# current-sensor.net
KiCad netlist of a schematic drawn in EAGLE
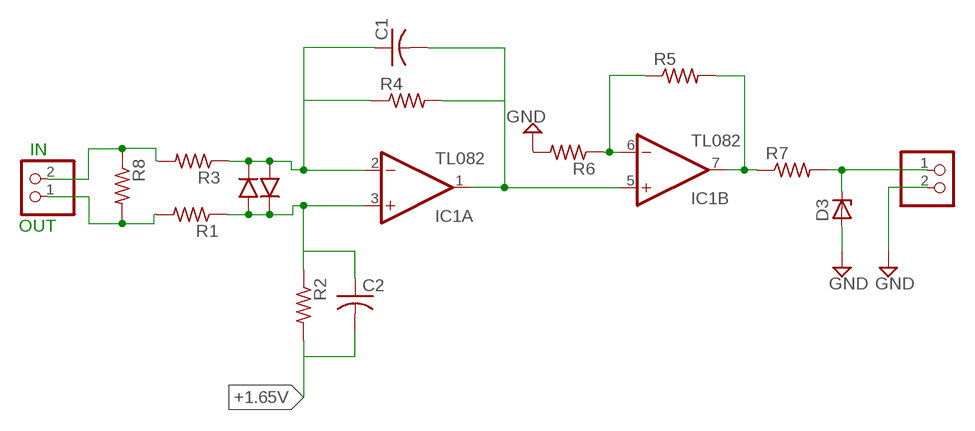
[diagram p0: schematic, sheet 1]

(export (version "E")
  (design (tool "Eeschema 10.0.6"))
  (components
    (comp (ref "C1")
      (value "C-US025-050X050")
      (footprint "eagle-import:C025-050X050")
      (libsource (lib "eagle-import") (part "C-US025-050X050"))
    )
    (comp (ref "C2")
      (value "C-US025-050X050")
      (footprint "eagle-import:C025-050X050")
      (libsource (lib "eagle-import") (part "C-US025-050X050"))
    )
    (comp (ref "D1")
      (value "1N4004")
      (footprint "eagle-import:DO41-10")
      (libsource (lib "eagle-import") (part "1N4004"))
    )
    (comp (ref "D2")
      (value "1N4004")
      (footprint "eagle-import:DO41-10")
      (libsource (lib "eagle-import") (part "1N4004"))
    )
    (comp (ref "D3")
      (value "ZENER-DIODEC1702-15")
      (footprint "eagle-import:C1702-15")
      (libsource (lib "eagle-import") (part "ZENER-DIODEC1702-15"))
    )
    (comp (ref "I/P")
      (value "PINHD-1X2/90")
      (footprint "eagle-import:1X02_90")
      (libsource (lib "eagle-import") (part "PINHD-1X2/90"))
    )
    (comp (ref "IC1")
      (value "TL082")
      (footprint "eagle-import:DIL08")
      (libsource (lib "eagle-import") (part "TL082P"))
    )
    (comp (ref "O/P")
      (value "PINHD-1X2")
      (footprint "eagle-import:1X02")
      (libsource (lib "eagle-import") (part "PINHD-1X2"))
    )
    (comp (ref "R1")
      (value "R-US_0207/10")
      (footprint "eagle-import:0207_10")
      (libsource (lib "eagle-import") (part "R-US_0207/10"))
    )
    (comp (ref "R2")
      (value "R-US_0207/10")
      (footprint "eagle-import:0207_10")
      (libsource (lib "eagle-import") (part "R-US_0207/10"))
    )
    (comp (ref "R3")
      (value "R-US_0207/10")
      (footprint "eagle-import:0207_10")
      (libsource (lib "eagle-import") (part "R-US_0207/10"))
    )
    (comp (ref "R4")
      (value "R-US_0207/10")
      (footprint "eagle-import:0207_10")
      (libsource (lib "eagle-import") (part "R-US_0207/10"))
    )
    (comp (ref "R5")
      (value "R-US_0207/10")
      (footprint "eagle-import:0207_10")
      (libsource (lib "eagle-import") (part "R-US_0207/10"))
    )
    (comp (ref "R6")
      (value "R-US_0207/10")
      (footprint "eagle-import:0207_10")
      (libsource (lib "eagle-import") (part "R-US_0207/10"))
    )
    (comp (ref "R7")
      (value "R-US_0207/10")
      (footprint "eagle-import:0207_10")
      (libsource (lib "eagle-import") (part "R-US_0207/10"))
    )
    (comp (ref "R8")
      (value "R-US_0207/10")
      (footprint "eagle-import:0207_10")
      (libsource (lib "eagle-import") (part "R-US_0207/10"))
    )
  )
  (nets
    (net (code "1") (name "+1.65V") (class "Default")
      (node (ref "C2") (pin "2") (pinfunction "2_2") (pintype "passive"))
      (node (ref "R2") (pin "2") (pinfunction "2_2") (pintype "passive"))
    )
    (net (code "2") (name "GND") (class "Default")
      (node (ref "D3") (pin "A") (pinfunction "A_A") (pintype "passive"))
      (node (ref "O/P") (pin "2") (pinfunction "2_2") (pintype "passive"))
      (node (ref "R6") (pin "2") (pinfunction "2_2") (pintype "passive"))
    )
    (net (code "3") (name "Net-(D3-PadC)") (class "Default")
      (node (ref "D3") (pin "C") (pinfunction "C_C") (pintype "passive"))
      (node (ref "O/P") (pin "1") (pinfunction "1_1") (pintype "passive"))
      (node (ref "R7") (pin "2") (pinfunction "2_2") (pintype "passive"))
    )
    (net (code "4") (name "Net-(I/P-Pad1)") (class "Default")
      (node (ref "I/P") (pin "1") (pinfunction "1_1") (pintype "passive"))
      (node (ref "R1") (pin "2") (pinfunction "2_2") (pintype "passive"))
      (node (ref "R8") (pin "2") (pinfunction "2_2") (pintype "passive"))
    )
    (net (code "5") (name "Net-(I/P-Pad2)") (class "Default")
      (node (ref "I/P") (pin "2") (pinfunction "2_2") (pintype "passive"))
      (node (ref "R8") (pin "1") (pinfunction "1_1") (pintype "passive"))
    )
    (net (code "6") (name "Net-(IC1A-+IN)") (class "Default")
      (node (ref "C2") (pin "1") (pinfunction "1_1") (pintype "passive"))
      (node (ref "D1") (pin "A") (pinfunction "A_A") (pintype "passive"))
      (node (ref "D2") (pin "C") (pinfunction "C_C") (pintype "passive"))
      (node (ref "IC1") (pin "3") (pinfunction "+IN_3") (pintype "input"))
      (node (ref "R1") (pin "1") (pinfunction "1_1") (pintype "passive"))
      (node (ref "R2") (pin "1") (pinfunction "1_1") (pintype "passive"))
    )
    (net (code "7") (name "Net-(IC1A--IN)") (class "Default")
      (node (ref "C1") (pin "1") (pinfunction "1_1") (pintype "passive"))
      (node (ref "D1") (pin "C") (pinfunction "C_C") (pintype "passive"))
      (node (ref "D2") (pin "A") (pinfunction "A_A") (pintype "passive"))
      (node (ref "IC1") (pin "2") (pinfunction "-IN_2") (pintype "input"))
      (node (ref "R3") (pin "1") (pinfunction "1_1") (pintype "passive"))
      (node (ref "R4") (pin "1") (pinfunction "1_1") (pintype "passive"))
    )
    (net (code "8") (name "Net-(IC1A-OUT)") (class "Default")
      (node (ref "C1") (pin "2") (pinfunction "2_2") (pintype "passive"))
      (node (ref "IC1") (pin "1") (pinfunction "OUT_1") (pintype "output"))
      (node (ref "IC1") (pin "5") (pinfunction "+IN_5") (pintype "input"))
      (node (ref "R4") (pin "2") (pinfunction "2_2") (pintype "passive"))
    )
    (net (code "9") (name "Net-(IC1B--IN)") (class "Default")
      (node (ref "IC1") (pin "6") (pinfunction "-IN_6") (pintype "input"))
      (node (ref "R5") (pin "1") (pinfunction "1_1") (pintype "passive"))
      (node (ref "R6") (pin "1") (pinfunction "1_1") (pintype "passive"))
    )
    (net (code "10") (name "Net-(IC1B-OUT)") (class "Default")
      (node (ref "IC1") (pin "7") (pinfunction "OUT_7") (pintype "output"))
      (node (ref "R5") (pin "2") (pinfunction "2_2") (pintype "passive"))
      (node (ref "R7") (pin "1") (pinfunction "1_1") (pintype "passive"))
    )
    (net (code "11") (name "unconnected-(R3-Pad2)") (class "Default")
      (node (ref "R3") (pin "2") (pinfunction "2_2") (pintype "passive"))
    )
  )
)
